# 04_Eeprom_Flash.net
KiCad netlist of a schematic drawn in Altium Designer
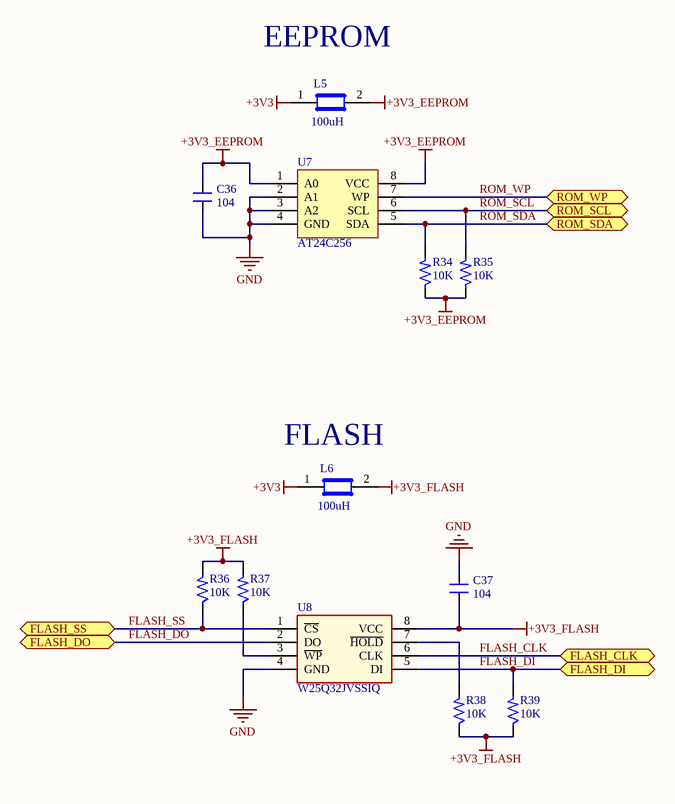
[diagram p0: [04] Eeprom_Flash.SchDoc]

(export (version "E")
  (design (tool "Eeschema 10.0.6"))
  (components
    (comp (ref "C36")
      (value "104")
      (footprint "C0603 SMT")
      (description "Cap SMD")
      (libsource (lib "khapham") (part "CM"))
    )
    (comp (ref "C37")
      (value "104")
      (footprint "C0603 SMT")
      (description "Cap SMD")
      (libsource (lib "khapham") (part "CM"))
    )
    (comp (ref "L5")
      (value "100uH")
      (footprint "R0805")
      (description "100uH 0805")
      (libsource (lib "khapham") (part "Ferrite Bead"))
    )
    (comp (ref "L6")
      (value "100uH")
      (footprint "R0805")
      (description "100uH 0805")
      (libsource (lib "khapham") (part "Ferrite Bead"))
    )
    (comp (ref "R34")
      (value "10K")
      (footprint "R0603 -SMT")
      (description "Resistor SMD")
      (libsource (lib "khapham") (part "RM"))
    )
    (comp (ref "R35")
      (value "10K")
      (footprint "R0603 -SMT")
      (description "Resistor SMD")
      (libsource (lib "khapham") (part "RM"))
    )
    (comp (ref "R36")
      (value "10K")
      (footprint "R0603 -SMT")
      (description "Resistor SMD")
      (libsource (lib "khapham") (part "RM"))
    )
    (comp (ref "R37")
      (value "10K")
      (footprint "R0603 -SMT")
      (description "Resistor SMD")
      (libsource (lib "khapham") (part "RM"))
    )
    (comp (ref "R38")
      (value "10K")
      (footprint "R0603 -SMT")
      (description "Resistor SMD")
      (libsource (lib "khapham") (part "RM"))
    )
    (comp (ref "R39")
      (value "10K")
      (footprint "R0603 -SMT")
      (description "Resistor SMD")
      (libsource (lib "khapham") (part "RM"))
    )
    (comp (ref "U7") (value "AT24C256") (footprint "SO-8") (libsource (lib "khapham") (part "AT24Cxx")))
    (comp (ref "U8")
      (value "W25Q32JVSSIQ")
      (footprint "SO-8 208")
      (description "FLASH 32MBIT 133MHZ 8SOP")
      (libsource (lib "khapham") (part "W25Q32JV"))
    )
  )
  (nets
    (net (code "1") (name "+3V3") (class "Default")
      (node (ref "L5") (pin "1") (pinfunction "1_1") (pintype "passive"))
      (node (ref "L6") (pin "1") (pinfunction "1_1") (pintype "passive"))
    )
    (net (code "2") (name "+3V3_EEPROM") (class "Default")
      (node (ref "C36") (pin "2") (pinfunction "2_2") (pintype "passive"))
      (node (ref "L5") (pin "2") (pinfunction "2_2") (pintype "passive"))
      (node (ref "R34") (pin "1") (pinfunction "1_1") (pintype "passive"))
      (node (ref "R35") (pin "1") (pinfunction "1_1") (pintype "passive"))
      (node (ref "U7") (pin "1") (pinfunction "A0_1") (pintype "passive"))
      (node (ref "U7") (pin "8") (pinfunction "VCC_8") (pintype "passive"))
    )
    (net (code "3") (name "+3V3_FLASH") (class "Default")
      (node (ref "C37") (pin "1") (pinfunction "1_1") (pintype "passive"))
      (node (ref "L6") (pin "2") (pinfunction "2_2") (pintype "passive"))
      (node (ref "R36") (pin "2") (pinfunction "2_2") (pintype "passive"))
      (node (ref "R37") (pin "2") (pinfunction "2_2") (pintype "passive"))
      (node (ref "R38") (pin "1") (pinfunction "1_1") (pintype "passive"))
      (node (ref "R39") (pin "1") (pinfunction "1_1") (pintype "passive"))
      (node (ref "U8") (pin "8") (pinfunction "VCC_8") (pintype "passive"))
    )
    (net (code "4") (name "/FLASH_CLK") (class "Default")
      (node (ref "U8") (pin "6") (pinfunction "CLK_6") (pintype "passive"))
    )
    (net (code "5") (name "/FLASH_DI") (class "Default")
      (node (ref "R39") (pin "2") (pinfunction "2_2") (pintype "passive"))
      (node (ref "U8") (pin "5") (pinfunction "DI_5") (pintype "passive"))
    )
    (net (code "6") (name "/FLASH_DO") (class "Default")
      (node (ref "U8") (pin "2") (pinfunction "DO_2") (pintype "passive"))
    )
    (net (code "7") (name "/FLASH_SS") (class "Default")
      (node (ref "R36") (pin "1") (pinfunction "1_1") (pintype "passive"))
      (node (ref "U8") (pin "1") (pinfunction "~{CS}_1") (pintype "passive"))
    )
    (net (code "8") (name "/ROM_SCL") (class "Default")
      (node (ref "R35") (pin "2") (pinfunction "2_2") (pintype "passive"))
      (node (ref "U7") (pin "6") (pinfunction "SCL_6") (pintype "passive"))
    )
    (net (code "9") (name "/ROM_SDA") (class "Default")
      (node (ref "R34") (pin "2") (pinfunction "2_2") (pintype "passive"))
      (node (ref "U7") (pin "5") (pinfunction "SDA_5") (pintype "passive"))
    )
    (net (code "10") (name "/ROM_WP") (class "Default")
      (node (ref "U7") (pin "7") (pinfunction "WP_7") (pintype "passive"))
    )
    (net (code "11") (name "GND") (class "Default")
      (node (ref "C36") (pin "1") (pinfunction "1_1") (pintype "passive"))
      (node (ref "C37") (pin "2") (pinfunction "2_2") (pintype "passive"))
      (node (ref "U7") (pin "2") (pinfunction "A1_2") (pintype "passive"))
      (node (ref "U7") (pin "3") (pinfunction "A2_3") (pintype "passive"))
      (node (ref "U7") (pin "4") (pinfunction "GND_4") (pintype "passive"))
      (node (ref "U8") (pin "4") (pinfunction "GND_4") (pintype "passive"))
    )
    (net (code "12") (name "Net-(U8-~{HOLD})") (class "Default")
      (node (ref "R38") (pin "2") (pinfunction "2_2") (pintype "passive"))
      (node (ref "U8") (pin "7") (pinfunction "~{HOLD}_7") (pintype "passive"))
    )
    (net (code "13") (name "Net-(U8-~{WP})") (class "Default")
      (node (ref "R37") (pin "1") (pinfunction "1_1") (pintype "passive"))
      (node (ref "U8") (pin "3") (pinfunction "~{WP}_3") (pintype "passive"))
    )
  )
)
